# Sheet1.net
KiCad netlist of a schematic drawn in Altium Designer
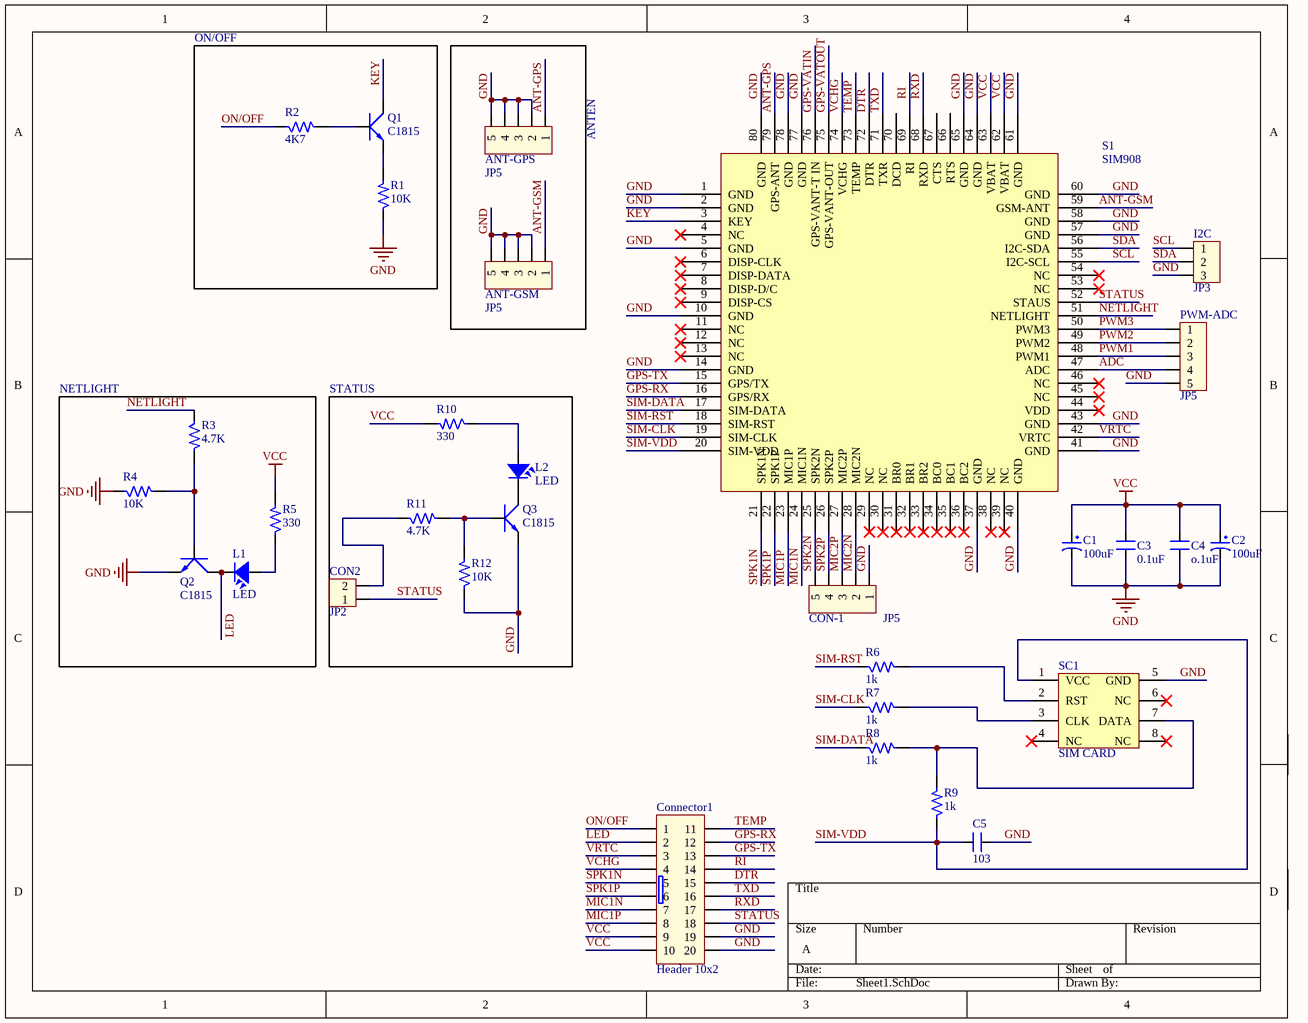
[diagram p0: Sheet1.SchDoc]

(export (version "E")
  (design (tool "Eeschema 10.0.6"))
  (components
    (comp (ref "ANT-GPS")
      (value "JP5")
      (footprint "MCX5.08-H5")
      (description "Connector 5")
      (libsource (lib "") (part "Con5_1"))
    )
    (comp (ref "ANT-GSM")
      (value "JP5")
      (footprint "MCX5.08-H5")
      (description "Connector 5")
      (libsource (lib "") (part "Con5_1"))
    )
    (comp (ref "C1")
      (value "100uF")
      (footprint "CAP-D8-220uF/16V")
      (description "Cap 10000uF/63V")
      (libsource (lib "syhaunguyen") (part "CP9"))
    )
    (comp (ref "C2")
      (value "100uF")
      (footprint "CAP-D8-220uF/16V")
      (description "Cap 10000uF/63V")
      (libsource (lib "syhaunguyen") (part "CP9"))
    )
    (comp (ref "C3")
      (value "0.1uF")
      (footprint "SM-0805")
      (description "Cap SMD")
      (libsource (lib "syhaunguyen") (part "CM"))
    )
    (comp (ref "C4")
      (value "o.1uF")
      (footprint "SM-0805")
      (description "Cap SMD")
      (libsource (lib "syhaunguyen") (part "CM"))
    )
    (comp (ref "C5")
      (value "103")
      (footprint "SM-0805")
      (description "Cap SMD")
      (libsource (lib "syhaunguyen") (part "CM"))
    )
    (comp (ref "CON-1")
      (value "JP5")
      (footprint "CON5")
      (description "Connector 5")
      (libsource (lib "") (part "Con5_1"))
    )
    (comp (ref "CON2")
      (value "JP2")
      (footprint "CON2")
      (description "Connector 2")
      (libsource (lib "syhaunguyen") (part "Con2"))
    )
    (comp (ref "Connector1")
      (value "Header 10x2")
      (footprint "Hed2X10")
      (libsource (lib "syhaunguyen") (part "HED10X2"))
    )
    (comp (ref "I2C")
      (value "JP3")
      (footprint "CON3")
      (description "Connector 3")
      (libsource (lib "syhaunguyen") (part "Con3"))
    )
    (comp (ref "L1")
      (value "LED")
      (footprint "SM-1206")
      (description "LED Single colour Green and Red")
      (libsource (lib "syhaunguyen") (part "LED"))
    )
    (comp (ref "L2")
      (value "LED")
      (footprint "LED-3")
      (description "LED Single colour Green and Red")
      (libsource (lib "syhaunguyen") (part "LED"))
    )
    (comp (ref "PWM-ADC")
      (value "JP5")
      (footprint "CON5")
      (description "Connector 5")
      (libsource (lib "syhaunguyen") (part "Con5"))
    )
    (comp (ref "Q1")
      (value "C1815")
      (footprint "2N2222")
      (description "NPN 600mW, ECB")
      (libsource (lib "syhaunguyen") (part "C1815"))
    )
    (comp (ref "Q2")
      (value "C1815")
      (footprint "2N2222")
      (description "NPN 600mW, ECB")
      (libsource (lib "syhaunguyen") (part "C1815"))
    )
    (comp (ref "Q3")
      (value "C1815")
      (footprint "QTO-92")
      (description "NPN 600mW, ECB")
      (libsource (lib "syhaunguyen") (part "C1815"))
    )
    (comp (ref "R1")
      (value "10K")
      (footprint "SM-0805")
      (description "Resistor 1/4W")
      (libsource (lib "syhaunguyen") (part "R"))
    )
    (comp (ref "R2")
      (value "4K7")
      (footprint "SM-0805")
      (description "Resistor 1/4W")
      (libsource (lib "syhaunguyen") (part "R"))
    )
    (comp (ref "R3")
      (value "4.7K")
      (footprint "SM-0805")
      (description "Resistor 1/4W")
      (libsource (lib "syhaunguyen") (part "R"))
    )
    (comp (ref "R4")
      (value "10K")
      (footprint "SM-0805")
      (description "Resistor 1/4W")
      (libsource (lib "syhaunguyen") (part "R"))
    )
    (comp (ref "R5")
      (value "330")
      (footprint "SM-0805")
      (description "Resistor 1/4W")
      (libsource (lib "syhaunguyen") (part "R"))
    )
    (comp (ref "R6")
      (value "1k")
      (footprint "SM-0805")
      (description "Resistor 1/4W")
      (libsource (lib "syhaunguyen") (part "R"))
    )
    (comp (ref "R7")
      (value "1k")
      (footprint "SM-0805")
      (description "Resistor 1/4W")
      (libsource (lib "syhaunguyen") (part "R"))
    )
    (comp (ref "R8")
      (value "1k")
      (footprint "SM-0805")
      (description "Resistor 1/4W")
      (libsource (lib "syhaunguyen") (part "R"))
    )
    (comp (ref "R9")
      (value "1k")
      (footprint "SM-0805")
      (description "Resistor 1/4W")
      (libsource (lib "syhaunguyen") (part "R"))
    )
    (comp (ref "R10")
      (value "330")
      (footprint "R1/4W")
      (description "Resistor 1/4W")
      (libsource (lib "syhaunguyen") (part "R"))
    )
    (comp (ref "R11")
      (value "4.7K")
      (footprint "R1/4W")
      (description "Resistor 1/4W")
      (libsource (lib "syhaunguyen") (part "R"))
    )
    (comp (ref "R12")
      (value "10K")
      (footprint "R1/4W")
      (description "Resistor 1/4W")
      (libsource (lib "syhaunguyen") (part "R"))
    )
    (comp (ref "S1") (value "SIM908") (footprint "SIM908") (libsource (lib "syhaunguyen") (part "SIM908")))
    (comp (ref "SC1")
      (value "SIM CARD")
      (footprint "SIM CARD")
      (libsource (lib "syhaunguyen") (part "SIM CARD"))
    )
  )
  (nets
    (net (code "1") (name "/ADC") (class "Default")
      (node (ref "PWM-ADC") (pin "4") (pinfunction "4_4") (pintype "passive"))
      (node (ref "S1") (pin "47") (pinfunction "ADC_47") (pintype "passive"))
    )
    (net (code "2") (name "/ANT-GPS") (class "Default")
      (node (ref "ANT-GPS") (pin "1") (pinfunction "1_1") (pintype "passive"))
      (node (ref "S1") (pin "79") (pinfunction "GPS-ANT_79") (pintype "passive"))
    )
    (net (code "3") (name "/ANT-GSM") (class "Default")
      (node (ref "ANT-GSM") (pin "1") (pinfunction "1_1") (pintype "passive"))
      (node (ref "S1") (pin "59") (pinfunction "GSM-ANT_59") (pintype "passive"))
    )
    (net (code "4") (name "/DTR") (class "Default")
      (node (ref "Connector1") (pin "15") (pinfunction "15_15") (pintype "passive"))
      (node (ref "S1") (pin "72") (pinfunction "DTR_72") (pintype "passive"))
    )
    (net (code "5") (name "/GPS-RX") (class "Default")
      (node (ref "Connector1") (pin "12") (pinfunction "12_12") (pintype "passive"))
      (node (ref "S1") (pin "16") (pinfunction "GPS/RX_16") (pintype "passive"))
    )
    (net (code "6") (name "/GPS-TX") (class "Default")
      (node (ref "Connector1") (pin "13") (pinfunction "13_13") (pintype "passive"))
      (node (ref "S1") (pin "15") (pinfunction "GPS/TX_15") (pintype "passive"))
    )
    (net (code "7") (name "/GPS-VATIN") (class "Default")
      (node (ref "S1") (pin "76") (pinfunction "GPS-VANT-T_IN_76") (pintype "passive"))
    )
    (net (code "8") (name "/GPS-VATOUT") (class "Default")
      (node (ref "S1") (pin "75") (pinfunction "GPS-VANT-OUT_75") (pintype "passive"))
    )
    (net (code "9") (name "/KEY") (class "Default")
      (node (ref "Q1") (pin "2") (pinfunction "C_2") (pintype "passive"))
      (node (ref "S1") (pin "3") (pinfunction "KEY_3") (pintype "passive"))
    )
    (net (code "10") (name "/LED") (class "Default")
      (node (ref "Connector1") (pin "2") (pinfunction "2_2") (pintype "passive"))
      (node (ref "L1") (pin "2") (pinfunction "2_2") (pintype "passive"))
      (node (ref "Q2") (pin "2") (pinfunction "C_2") (pintype "passive"))
    )
    (net (code "11") (name "/MIC1N") (class "Default")
      (node (ref "Connector1") (pin "7") (pinfunction "7_7") (pintype "passive"))
      (node (ref "S1") (pin "24") (pinfunction "MIC1N_24") (pintype "passive"))
    )
    (net (code "12") (name "/MIC1P") (class "Default")
      (node (ref "Connector1") (pin "8") (pinfunction "8_8") (pintype "passive"))
      (node (ref "S1") (pin "23") (pinfunction "MIC1P_23") (pintype "passive"))
    )
    (net (code "13") (name "/MIC2N") (class "Default")
      (node (ref "CON-1") (pin "2") (pinfunction "2_2") (pintype "passive"))
      (node (ref "S1") (pin "28") (pinfunction "MIC2N_28") (pintype "passive"))
    )
    (net (code "14") (name "/MIC2P") (class "Default")
      (node (ref "CON-1") (pin "3") (pinfunction "3_3") (pintype "passive"))
      (node (ref "S1") (pin "27") (pinfunction "MIC2P_27") (pintype "passive"))
    )
    (net (code "15") (name "/NETLIGHT") (class "Default")
      (node (ref "R3") (pin "1") (pinfunction "1_1") (pintype "passive"))
      (node (ref "S1") (pin "51") (pinfunction "NETLIGHT_51") (pintype "passive"))
    )
    (net (code "16") (name "/ON{slash}OFF") (class "Default")
      (node (ref "Connector1") (pin "1") (pinfunction "1_1") (pintype "passive"))
      (node (ref "R2") (pin "1") (pinfunction "1_1") (pintype "passive"))
    )
    (net (code "17") (name "/PWM1") (class "Default")
      (node (ref "PWM-ADC") (pin "3") (pinfunction "3_3") (pintype "passive"))
      (node (ref "S1") (pin "48") (pinfunction "PWM1_48") (pintype "passive"))
    )
    (net (code "18") (name "/PWM2") (class "Default")
      (node (ref "PWM-ADC") (pin "2") (pinfunction "2_2") (pintype "passive"))
      (node (ref "S1") (pin "49") (pinfunction "PWM2_49") (pintype "passive"))
    )
    (net (code "19") (name "/PWM3") (class "Default")
      (node (ref "PWM-ADC") (pin "1") (pinfunction "1_1") (pintype "passive"))
      (node (ref "S1") (pin "50") (pinfunction "PWM3_50") (pintype "passive"))
    )
    (net (code "20") (name "/RI") (class "Default")
      (node (ref "Connector1") (pin "14") (pinfunction "14_14") (pintype "passive"))
      (node (ref "S1") (pin "69") (pinfunction "RI_69") (pintype "passive"))
    )
    (net (code "21") (name "/RXD") (class "Default")
      (node (ref "Connector1") (pin "17") (pinfunction "17_17") (pintype "passive"))
      (node (ref "S1") (pin "68") (pinfunction "RXD_68") (pintype "passive"))
    )
    (net (code "22") (name "/SCL") (class "Default")
      (node (ref "I2C") (pin "1") (pinfunction "1_1") (pintype "passive"))
      (node (ref "S1") (pin "55") (pinfunction "I2C-SCL_55") (pintype "passive"))
    )
    (net (code "23") (name "/SDA") (class "Default")
      (node (ref "I2C") (pin "2") (pinfunction "2_2") (pintype "passive"))
      (node (ref "S1") (pin "56") (pinfunction "I2C-SDA_56") (pintype "passive"))
    )
    (net (code "24") (name "/SIM-CLK") (class "Default")
      (node (ref "R7") (pin "1") (pinfunction "1_1") (pintype "passive"))
      (node (ref "S1") (pin "19") (pinfunction "SIM-CLK_19") (pintype "passive"))
    )
    (net (code "25") (name "/SIM-DATA") (class "Default")
      (node (ref "R8") (pin "1") (pinfunction "1_1") (pintype "passive"))
      (node (ref "S1") (pin "17") (pinfunction "SIM-DATA_17") (pintype "passive"))
    )
    (net (code "26") (name "/SIM-RST") (class "Default")
      (node (ref "R6") (pin "1") (pinfunction "1_1") (pintype "passive"))
      (node (ref "S1") (pin "18") (pinfunction "SIM-RST_18") (pintype "passive"))
    )
    (net (code "27") (name "/SIM-VDD") (class "Default")
      (node (ref "C5") (pin "1") (pinfunction "1_1") (pintype "passive"))
      (node (ref "R9") (pin "1") (pinfunction "1_1") (pintype "passive"))
      (node (ref "S1") (pin "20") (pinfunction "SIM-VDD_20") (pintype "passive"))
      (node (ref "SC1") (pin "1") (pinfunction "VCC_1") (pintype "passive"))
    )
    (net (code "28") (name "/SPK1N") (class "Default")
      (node (ref "Connector1") (pin "5") (pinfunction "5_5") (pintype "passive"))
      (node (ref "S1") (pin "21") (pinfunction "SPK1N_21") (pintype "passive"))
    )
    (net (code "29") (name "/SPK1P") (class "Default")
      (node (ref "Connector1") (pin "6") (pinfunction "6_6") (pintype "passive"))
      (node (ref "S1") (pin "22") (pinfunction "SPK1P_22") (pintype "passive"))
    )
    (net (code "30") (name "/SPK2N") (class "Default")
      (node (ref "CON-1") (pin "5") (pinfunction "5_5") (pintype "passive"))
      (node (ref "S1") (pin "25") (pinfunction "SPK2N_25") (pintype "passive"))
    )
    (net (code "31") (name "/SPK2P") (class "Default")
      (node (ref "CON-1") (pin "4") (pinfunction "4_4") (pintype "passive"))
      (node (ref "S1") (pin "26") (pinfunction "SPK2P_26") (pintype "passive"))
    )
    (net (code "32") (name "/STATUS") (class "Default")
      (node (ref "CON2") (pin "1") (pinfunction "1_1") (pintype "passive"))
      (node (ref "Connector1") (pin "18") (pinfunction "18_18") (pintype "passive"))
      (node (ref "S1") (pin "52") (pinfunction "STAUS_52") (pintype "passive"))
    )
    (net (code "33") (name "/TEMP") (class "Default")
      (node (ref "Connector1") (pin "11") (pinfunction "11_11") (pintype "passive"))
      (node (ref "S1") (pin "73") (pinfunction "TEMP_73") (pintype "passive"))
    )
    (net (code "34") (name "/TXD") (class "Default")
      (node (ref "Connector1") (pin "16") (pinfunction "16_16") (pintype "passive"))
      (node (ref "S1") (pin "71") (pinfunction "TXR_71") (pintype "passive"))
    )
    (net (code "35") (name "/VCHG") (class "Default")
      (node (ref "Connector1") (pin "4") (pinfunction "4_4") (pintype "passive"))
      (node (ref "S1") (pin "74") (pinfunction "VCHG_74") (pintype "passive"))
    )
    (net (code "36") (name "/VRTC") (class "Default")
      (node (ref "Connector1") (pin "3") (pinfunction "3_3") (pintype "passive"))
      (node (ref "S1") (pin "42") (pinfunction "VRTC_42") (pintype "passive"))
    )
    (net (code "37") (name "GND") (class "Default")
      (node (ref "ANT-GPS") (pin "2") (pinfunction "2_2") (pintype "passive"))
      (node (ref "ANT-GPS") (pin "3") (pinfunction "3_3") (pintype "passive"))
      (node (ref "ANT-GPS") (pin "4") (pinfunction "4_4") (pintype "passive"))
      (node (ref "ANT-GPS") (pin "5") (pinfunction "5_5") (pintype "passive"))
      (node (ref "ANT-GSM") (pin "2") (pinfunction "2_2") (pintype "passive"))
      (node (ref "ANT-GSM") (pin "3") (pinfunction "3_3") (pintype "passive"))
      (node (ref "ANT-GSM") (pin "4") (pinfunction "4_4") (pintype "passive"))
      (node (ref "ANT-GSM") (pin "5") (pinfunction "5_5") (pintype "passive"))
      (node (ref "C1") (pin "2") (pinfunction "2_2") (pintype "passive"))
      (node (ref "C2") (pin "2") (pinfunction "2_2") (pintype "passive"))
      (node (ref "C3") (pin "1") (pinfunction "1_1") (pintype "passive"))
      (node (ref "C4") (pin "1") (pinfunction "1_1") (pintype "passive"))
      (node (ref "C5") (pin "2") (pinfunction "2_2") (pintype "passive"))
      (node (ref "CON-1") (pin "1") (pinfunction "1_1") (pintype "passive"))
      (node (ref "Connector1") (pin "19") (pinfunction "19_19") (pintype "passive"))
      (node (ref "Connector1") (pin "20") (pinfunction "20_20") (pintype "passive"))
      (node (ref "I2C") (pin "3") (pinfunction "3_3") (pintype "passive"))
      (node (ref "PWM-ADC") (pin "5") (pinfunction "5_5") (pintype "passive"))
      (node (ref "Q2") (pin "1") (pinfunction "E_1") (pintype "passive"))
      (node (ref "Q3") (pin "1") (pinfunction "E_1") (pintype "passive"))
      (node (ref "R1") (pin "1") (pinfunction "1_1") (pintype "passive"))
      (node (ref "R12") (pin "1") (pinfunction "1_1") (pintype "passive"))
      (node (ref "R4") (pin "1") (pinfunction "1_1") (pintype "passive"))
      (node (ref "S1") (pin "1") (pinfunction "GND_1") (pintype "passive"))
      (node (ref "S1") (pin "10") (pinfunction "GND_10") (pintype "passive"))
      (node (ref "S1") (pin "14") (pinfunction "GND_14") (pintype "passive"))
      (node (ref "S1") (pin "2") (pinfunction "GND_2") (pintype "passive"))
      (node (ref "S1") (pin "37") (pinfunction "GND_37") (pintype "passive"))
      (node (ref "S1") (pin "40") (pinfunction "GND_40") (pintype "passive"))
      (node (ref "S1") (pin "41") (pinfunction "GND_41") (pintype "passive"))
      (node (ref "S1") (pin "43") (pinfunction "GND_43") (pintype "passive"))
      (node (ref "S1") (pin "5") (pinfunction "GND_5") (pintype "passive"))
      (node (ref "S1") (pin "57") (pinfunction "GND_57") (pintype "passive"))
      (node (ref "S1") (pin "58") (pinfunction "GND_58") (pintype "passive"))
      (node (ref "S1") (pin "60") (pinfunction "GND_60") (pintype "passive"))
      (node (ref "S1") (pin "61") (pinfunction "GND_61") (pintype "passive"))
      (node (ref "S1") (pin "64") (pinfunction "GND_64") (pintype "passive"))
      (node (ref "S1") (pin "65") (pinfunction "GND_65") (pintype "passive"))
      (node (ref "S1") (pin "77") (pinfunction "GND_77") (pintype "passive"))
      (node (ref "S1") (pin "78") (pinfunction "GND_78") (pintype "passive"))
      (node (ref "S1") (pin "80") (pinfunction "GND_80") (pintype "passive"))
      (node (ref "SC1") (pin "5") (pinfunction "GND_5") (pintype "passive"))
    )
    (net (code "38") (name "Net-(CON2-Pad2)") (class "Default")
      (node (ref "CON2") (pin "2") (pinfunction "2_2") (pintype "passive"))
      (node (ref "R11") (pin "1") (pinfunction "1_1") (pintype "passive"))
    )
    (net (code "39") (name "Net-(L1-Pad1)") (class "Default")
      (node (ref "L1") (pin "1") (pinfunction "1_1") (pintype "passive"))
      (node (ref "R5") (pin "1") (pinfunction "1_1") (pintype "passive"))
    )
    (net (code "40") (name "Net-(L2-Pad1)") (class "Default")
      (node (ref "L2") (pin "1") (pinfunction "1_1") (pintype "passive"))
      (node (ref "R10") (pin "1") (pinfunction "1_1") (pintype "passive"))
    )
    (net (code "41") (name "Net-(Q1-B)") (class "Default")
      (node (ref "Q1") (pin "3") (pinfunction "B_3") (pintype "passive"))
      (node (ref "R2") (pin "2") (pinfunction "2_2") (pintype "passive"))
    )
    (net (code "42") (name "Net-(Q1-E)") (class "Default")
      (node (ref "Q1") (pin "1") (pinfunction "E_1") (pintype "passive"))
      (node (ref "R1") (pin "2") (pinfunction "2_2") (pintype "passive"))
    )
    (net (code "43") (name "Net-(Q2-B)") (class "Default")
      (node (ref "Q2") (pin "3") (pinfunction "B_3") (pintype "passive"))
      (node (ref "R3") (pin "2") (pinfunction "2_2") (pintype "passive"))
      (node (ref "R4") (pin "2") (pinfunction "2_2") (pintype "passive"))
    )
    (net (code "44") (name "Net-(Q3-B)") (class "Default")
      (node (ref "Q3") (pin "3") (pinfunction "B_3") (pintype "passive"))
      (node (ref "R11") (pin "2") (pinfunction "2_2") (pintype "passive"))
      (node (ref "R12") (pin "2") (pinfunction "2_2") (pintype "passive"))
    )
    (net (code "45") (name "Net-(Q3-C)") (class "Default")
      (node (ref "L2") (pin "2") (pinfunction "2_2") (pintype "passive"))
      (node (ref "Q3") (pin "2") (pinfunction "C_2") (pintype "passive"))
    )
    (net (code "46") (name "Net-(SC1-CLK)") (class "Default")
      (node (ref "R7") (pin "2") (pinfunction "2_2") (pintype "passive"))
      (node (ref "SC1") (pin "3") (pinfunction "CLK_3") (pintype "passive"))
    )
    (net (code "47") (name "Net-(SC1-DATA)") (class "Default")
      (node (ref "R8") (pin "2") (pinfunction "2_2") (pintype "passive"))
      (node (ref "R9") (pin "2") (pinfunction "2_2") (pintype "passive"))
      (node (ref "SC1") (pin "7") (pinfunction "DATA_7") (pintype "passive"))
    )
    (net (code "48") (name "Net-(SC1-RST)") (class "Default")
      (node (ref "R6") (pin "2") (pinfunction "2_2") (pintype "passive"))
      (node (ref "SC1") (pin "2") (pinfunction "RST_2") (pintype "passive"))
    )
    (net (code "49") (name "VCC") (class "Default")
      (node (ref "C1") (pin "1") (pinfunction "1_1") (pintype "passive"))
      (node (ref "C2") (pin "1") (pinfunction "1_1") (pintype "passive"))
      (node (ref "C3") (pin "2") (pinfunction "2_2") (pintype "passive"))
      (node (ref "C4") (pin "2") (pinfunction "2_2") (pintype "passive"))
      (node (ref "Connector1") (pin "10") (pinfunction "10_10") (pintype "passive"))
      (node (ref "Connector1") (pin "9") (pinfunction "9_9") (pintype "passive"))
      (node (ref "R10") (pin "2") (pinfunction "2_2") (pintype "passive"))
      (node (ref "R5") (pin "2") (pinfunction "2_2") (pintype "passive"))
      (node (ref "S1") (pin "62") (pinfunction "VBAT_62") (pintype "passive"))
      (node (ref "S1") (pin "63") (pinfunction "VBAT_63") (pintype "passive"))
    )
    (net (code "50") (name "unconnected-(S1-BC0-Pad34)") (class "Default")
      (node (ref "S1") (pin "34") (pinfunction "BC0_34") (pintype "passive+no_connect"))
    )
    (net (code "51") (name "unconnected-(S1-BC1-Pad35)") (class "Default")
      (node (ref "S1") (pin "35") (pinfunction "BC1_35") (pintype "passive+no_connect"))
    )
    (net (code "52") (name "unconnected-(S1-BC2-Pad36)") (class "Default")
      (node (ref "S1") (pin "36") (pinfunction "BC2_36") (pintype "passive+no_connect"))
    )
    (net (code "53") (name "unconnected-(S1-BR0-Pad31)") (class "Default")
      (node (ref "S1") (pin "31") (pinfunction "BR0_31") (pintype "passive+no_connect"))
    )
    (net (code "54") (name "unconnected-(S1-BR1-Pad32)") (class "Default")
      (node (ref "S1") (pin "32") (pinfunction "BR1_32") (pintype "passive+no_connect"))
    )
    (net (code "55") (name "unconnected-(S1-BR2-Pad33)") (class "Default")
      (node (ref "S1") (pin "33") (pinfunction "BR2_33") (pintype "passive+no_connect"))
    )
    (net (code "56") (name "unconnected-(S1-CTS-Pad67)") (class "Default")
      (node (ref "S1") (pin "67") (pinfunction "CTS_67") (pintype "passive"))
    )
    (net (code "57") (name "unconnected-(S1-DCD-Pad70)") (class "Default")
      (node (ref "S1") (pin "70") (pinfunction "DCD_70") (pintype "passive"))
    )
    (net (code "58") (name "unconnected-(S1-DISP-CLK-Pad6)") (class "Default")
      (node (ref "S1") (pin "6") (pinfunction "DISP-CLK_6") (pintype "passive+no_connect"))
    )
    (net (code "59") (name "unconnected-(S1-DISP-CS-Pad9)") (class "Default")
      (node (ref "S1") (pin "9") (pinfunction "DISP-CS_9") (pintype "passive+no_connect"))
    )
    (net (code "60") (name "unconnected-(S1-DISP-DATA-Pad7)") (class "Default")
      (node (ref "S1") (pin "7") (pinfunction "DISP-DATA_7") (pintype "passive+no_connect"))
    )
    (net (code "61") (name "unconnected-(S1-DISP-D{slash}C-Pad8)") (class "Default")
      (node (ref "S1") (pin "8") (pinfunction "DISP-D/C_8") (pintype "passive+no_connect"))
    )
    (net (code "62") (name "unconnected-(S1-NC-Pad4)") (class "Default")
      (node (ref "S1") (pin "4") (pinfunction "NC_4") (pintype "passive+no_connect"))
    )
    (net (code "63") (name "unconnected-(S1-NC-Pad11)") (class "Default")
      (node (ref "S1") (pin "11") (pinfunction "NC_11") (pintype "passive+no_connect"))
    )
    (net (code "64") (name "unconnected-(S1-NC-Pad12)") (class "Default")
      (node (ref "S1") (pin "12") (pinfunction "NC_12") (pintype "passive+no_connect"))
    )
    (net (code "65") (name "unconnected-(S1-NC-Pad13)") (class "Default")
      (node (ref "S1") (pin "13") (pinfunction "NC_13") (pintype "passive+no_connect"))
    )
    (net (code "66") (name "unconnected-(S1-NC-Pad29)") (class "Default")
      (node (ref "S1") (pin "29") (pinfunction "NC_29") (pintype "passive+no_connect"))
    )
    (net (code "67") (name "unconnected-(S1-NC-Pad30)") (class "Default")
      (node (ref "S1") (pin "30") (pinfunction "NC_30") (pintype "passive+no_connect"))
    )
    (net (code "68") (name "unconnected-(S1-NC-Pad38)") (class "Default")
      (node (ref "S1") (pin "38") (pinfunction "NC_38") (pintype "passive+no_connect"))
    )
    (net (code "69") (name "unconnected-(S1-NC-Pad39)") (class "Default")
      (node (ref "S1") (pin "39") (pinfunction "NC_39") (pintype "passive+no_connect"))
    )
    (net (code "70") (name "unconnected-(S1-NC-Pad45)") (class "Default")
      (node (ref "S1") (pin "45") (pinfunction "NC_45") (pintype "passive+no_connect"))
    )
    (net (code "71") (name "unconnected-(S1-NC-Pad46)") (class "Default")
      (node (ref "S1") (pin "46") (pinfunction "NC_46") (pintype "passive+no_connect"))
    )
    (net (code "72") (name "unconnected-(S1-NC-Pad53)") (class "Default")
      (node (ref "S1") (pin "53") (pinfunction "NC_53") (pintype "passive+no_connect"))
    )
    (net (code "73") (name "unconnected-(S1-NC-Pad54)") (class "Default")
      (node (ref "S1") (pin "54") (pinfunction "NC_54") (pintype "passive+no_connect"))
    )
    (net (code "74") (name "unconnected-(S1-RTS-Pad66)") (class "Default")
      (node (ref "S1") (pin "66") (pinfunction "RTS_66") (pintype "passive"))
    )
    (net (code "75") (name "unconnected-(S1-VDD-Pad44)") (class "Default")
      (node (ref "S1") (pin "44") (pinfunction "VDD_44") (pintype "passive+no_connect"))
    )
    (net (code "76") (name "unconnected-(SC1-NC-Pad4)") (class "Default")
      (node (ref "SC1") (pin "4") (pinfunction "NC_4") (pintype "passive+no_connect"))
    )
    (net (code "77") (name "unconnected-(SC1-NC-Pad6)") (class "Default")
      (node (ref "SC1") (pin "6") (pinfunction "NC_6") (pintype "passive+no_connect"))
    )
    (net (code "78") (name "unconnected-(SC1-NC-Pad8)") (class "Default")
      (node (ref "SC1") (pin "8") (pinfunction "NC_8") (pintype "passive+no_connect"))
    )
  )
)
